# IR_sensor.net
KiCad netlist of a schematic drawn in Altium Designer
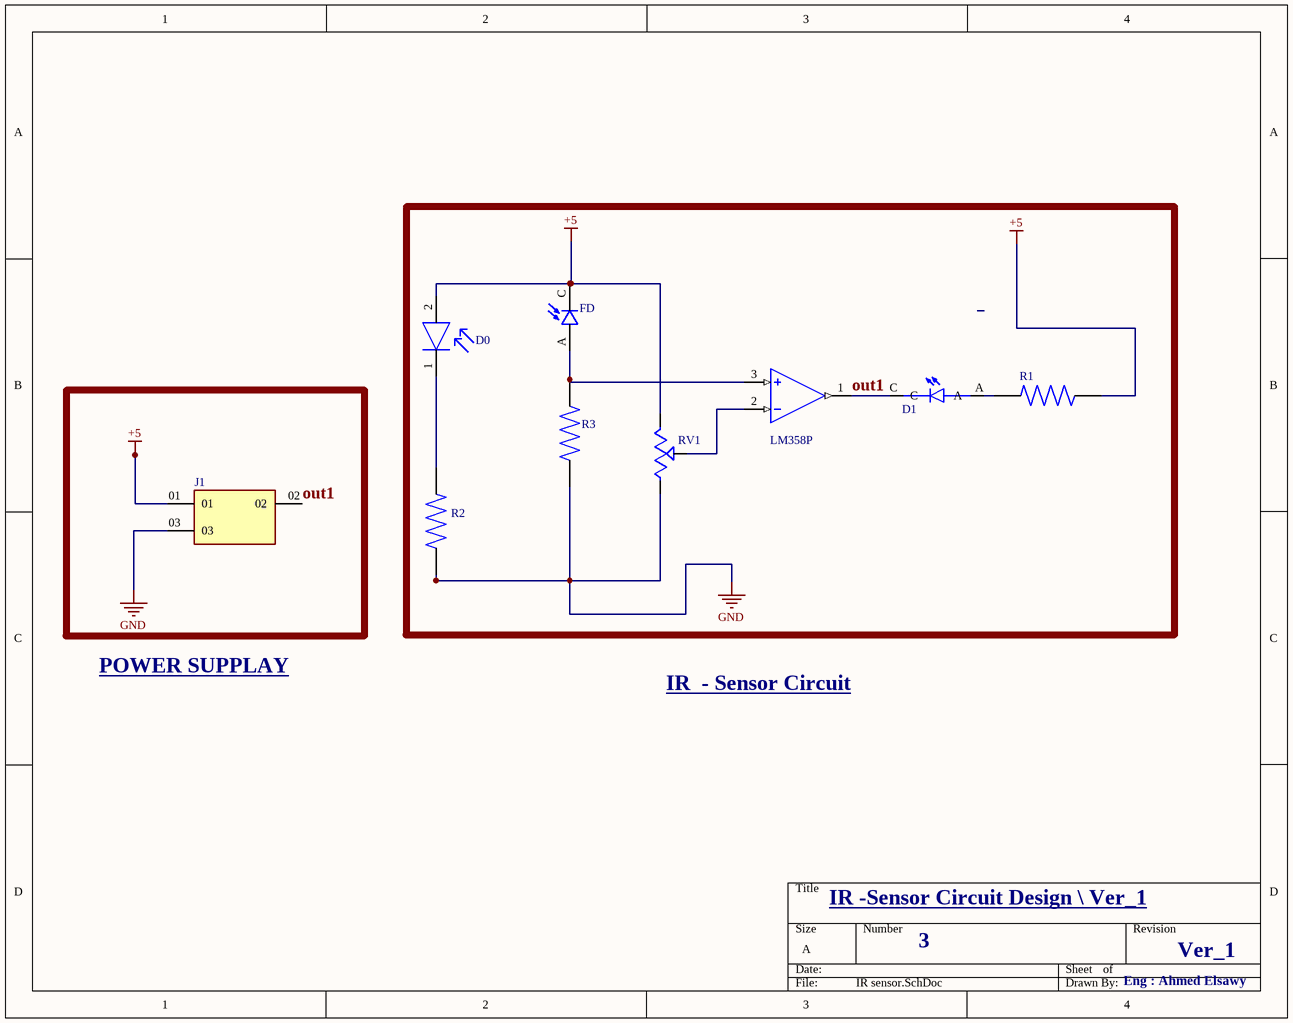
[diagram p0: IR sensor.SchDoc]

(export (version "E")
  (design (tool "Eeschema 10.0.6"))
  (components
    (comp (ref "D0")
      (value "BPV10")
      (footprint "Vishay_6.544-5185.02-4_MFG")
      (libsource (lib "Diode_Vishay_BPV10_eec") (part "BPV10"))
    )
    (comp (ref "D1")
      (value "WP7113ID")
      (footprint "LED_WP7113ID")
      (description "Red 617nm LED Indication - Discrete 2V Radial")
      (fields (field (name "MF") "Kingbright"))
      (libsource (lib "WP7113ID") (part "WP7113ID"))
    )
    (comp (ref "FD")
      (value "BPV10NF")
      (footprint "XDCR_BPV10NF")
      (description "Photodiodes T-1.75 790 to 1050nm +/-20 deg")
      (fields (field (name "MF") "Vishay Semiconductors"))
      (libsource (lib "BPV10NF") (part "BPV10NF"))
    )
    (comp (ref "J1")
      (value "TSW-101-07-T-T")
      (footprint "SAMTEC_TSW-101-07-T-T")
      (fields (field (name "MF") "Samtec"))
      (libsource (lib "TSW-101-07-T-T") (part "TSW-101-07-T-T"))
    )
    (comp (ref "LM358P")
      (value "LM358P")
      (footprint "DIP794W45P254L959H508Q8")
      (description "Dual, 30-V, 700-kHz operational amplifier")
      (fields (field (name "MF") "Texas Instruments"))
      (libsource (lib "LM358P") (part "LM358P"))
    )
    (comp (ref "R1")
      (value "ERJP08F3300V")
      (footprint "RES_ERJP08F3300V")
      (libsource (lib "ERJP08F3300V") (part "ERJP08F3300V"))
    )
    (comp (ref "R2")
      (value "100")
      (footprint "RESC1608X55N")
      (description "CRGH0603 5% 100R 0.2W")
      (fields (field (name "MP") "CRGH0603J100R"))
      (libsource (lib "CRGH0603J100R") (part "CRGH0603J100R"))
    )
    (comp (ref "R3")
      (value "ERA3ARB103V")
      (footprint "RES_ERA3ARB103V")
      (libsource (lib "ERA3ARB103V") (part "ERA3ARB103V"))
    )
    (comp (ref "RV1")
      (value "EVN-D8AA03B14")
      (footprint "TRIM_EVN-D8AA03B14")
      (description "10 kOhms 0.1W, 1/10W PC Pins Through Hole Trimmer Potentiometer Carbon 1.0 Turn Top Adjustment")
      (fields (field (name "MF") "Panasonic Electronic"))
      (libsource (lib "EVN-D8AA03B14") (part "EVN-D8AA03B14"))
    )
  )
  (nets
    (net (code "1") (name "+5") (class "Default")
      (node (ref "D0") (pin "2") (pinfunction "A_2") (pintype "passive"))
      (node (ref "FD") (pin "C") (pinfunction "C_C") (pintype "passive"))
      (node (ref "J1") (pin "01") (pinfunction "01_01") (pintype "passive"))
      (node (ref "R1") (pin "2") (pinfunction "2_2") (pintype "passive"))
      (node (ref "RV1") (pin "3") (pinfunction "3_3") (pintype "passive"))
    )
    (net (code "2") (name "/out1") (class "Default")
      (node (ref "D1") (pin "C") (pinfunction "C_C") (pintype "passive"))
      (node (ref "J1") (pin "02") (pinfunction "02_02") (pintype "passive"))
      (node (ref "LM358P") (pin "1") (pinfunction "OUT1_1") (pintype "output"))
    )
    (net (code "3") (name "GND") (class "Default")
      (node (ref "J1") (pin "03") (pinfunction "03_03") (pintype "passive"))
      (node (ref "R2") (pin "1") (pinfunction "1_1") (pintype "passive"))
      (node (ref "R3") (pin "1") (pinfunction "1_1") (pintype "passive"))
      (node (ref "RV1") (pin "1") (pinfunction "1_1") (pintype "passive"))
    )
    (net (code "4") (name "Net-(D0-C)") (class "Default")
      (node (ref "D0") (pin "1") (pinfunction "C_1") (pintype "passive"))
      (node (ref "R2") (pin "2") (pinfunction "2_2") (pintype "passive"))
    )
    (net (code "5") (name "Net-(D1-PadA)") (class "Default")
      (node (ref "D1") (pin "A") (pinfunction "A_A") (pintype "passive"))
      (node (ref "R1") (pin "1") (pinfunction "1_1") (pintype "passive"))
    )
    (net (code "6") (name "Net-(LM358PA-+IN1)") (class "Default")
      (node (ref "FD") (pin "A") (pinfunction "A_A") (pintype "passive"))
      (node (ref "LM358P") (pin "3") (pinfunction "+IN1_3") (pintype "input"))
      (node (ref "R3") (pin "2") (pinfunction "2_2") (pintype "passive"))
    )
    (net (code "7") (name "Net-(LM358PA--IN1)") (class "Default")
      (node (ref "LM358P") (pin "2") (pinfunction "-IN1_2") (pintype "input"))
      (node (ref "RV1") (pin "2") (pinfunction "2_2") (pintype "passive"))
    )
  )
)
